# FD_Capacitance_Sensor_v09.net
KiCad netlist of a schematic drawn in EAGLE
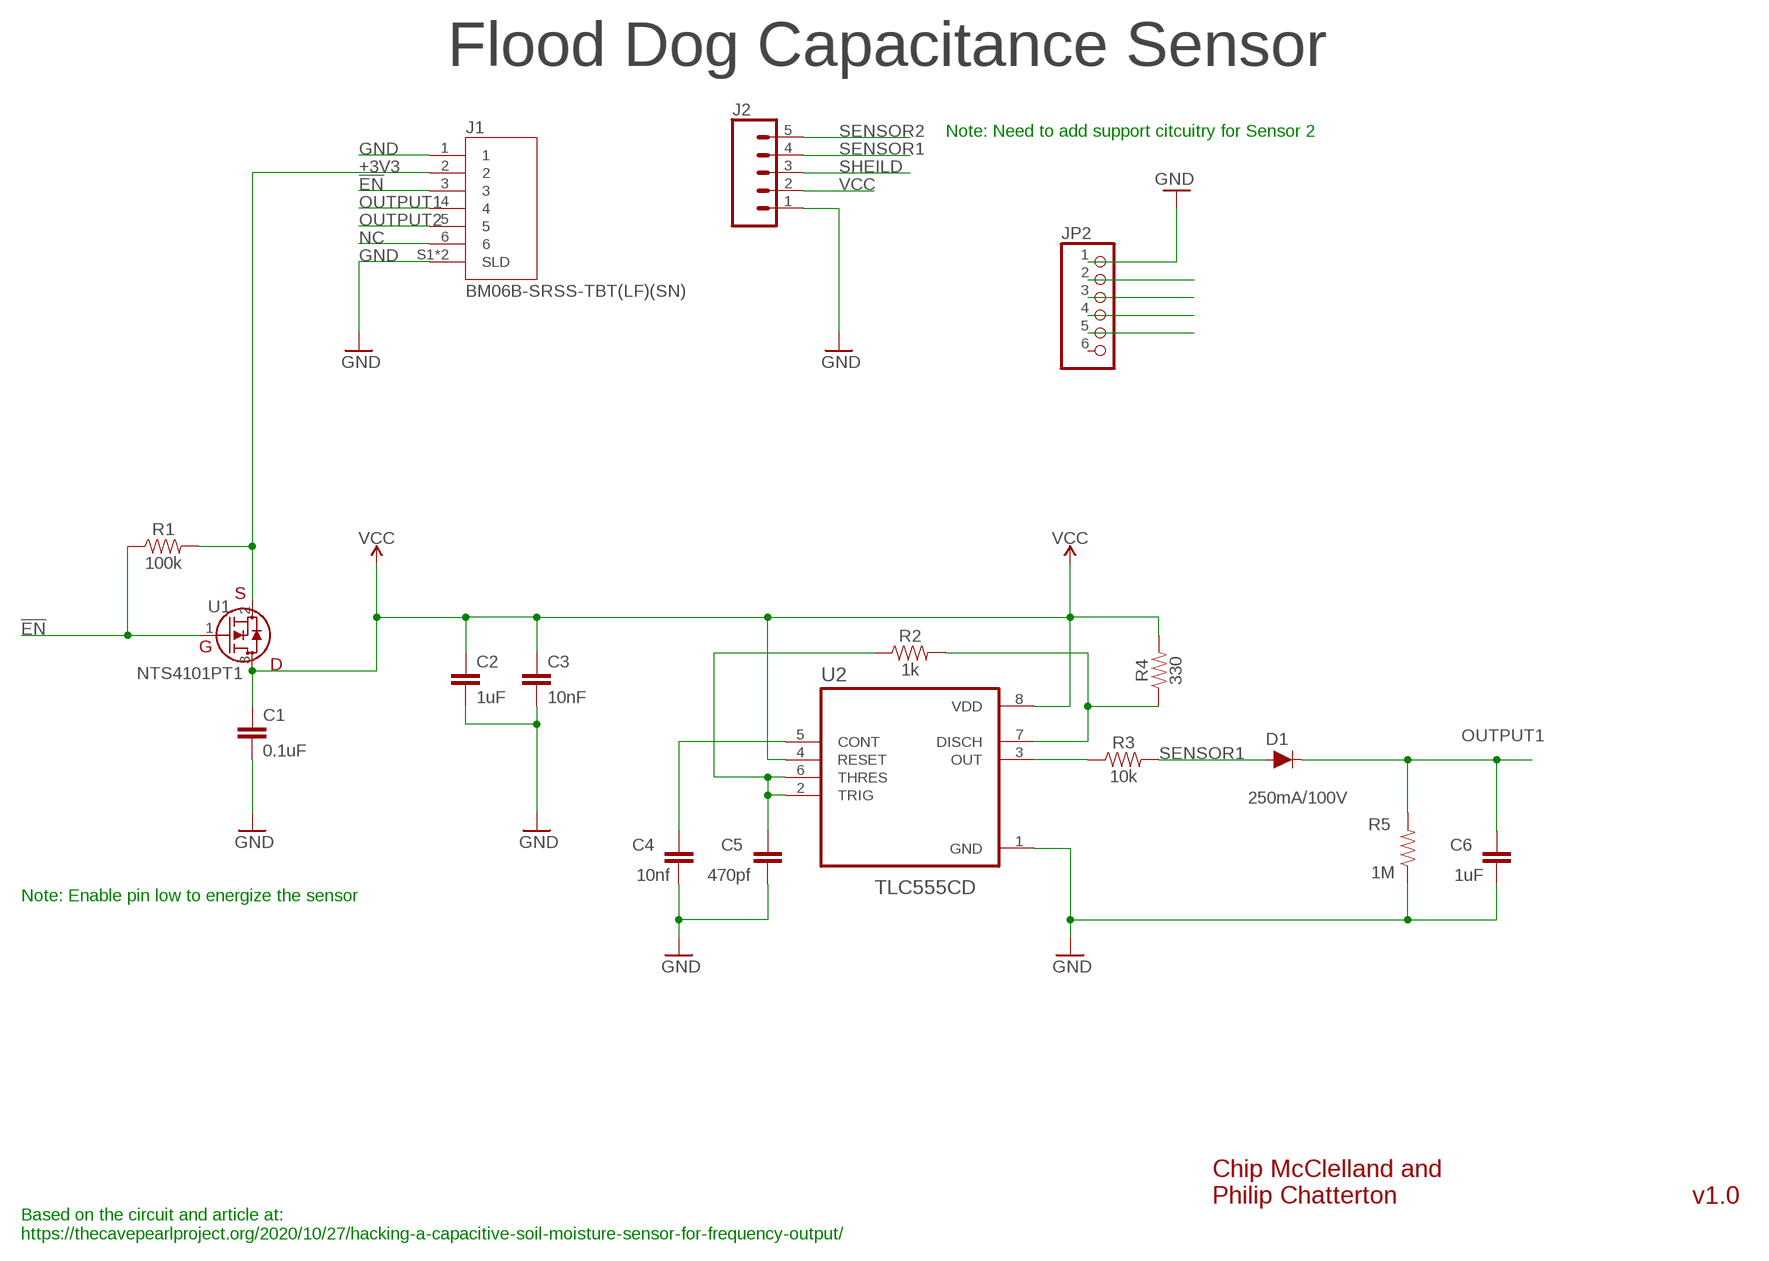
[diagram p0: schematic, sheet 1]

(export (version "E")
  (design (tool "Eeschema 10.0.6"))
  (components
    (comp (ref "C1")
      (value "0.1uF")
      (footprint "eagle-import:0805@1")
      (fields (field (name "HOUSEPART") "YES") (field (name "MPN") "MF-CAP-0805-0.1uF"))
      (libsource (lib "eagle-import") (part "CAP-MF-0.1UF-0805"))
    )
    (comp (ref "C2")
      (value "1uF")
      (footprint "eagle-import:0805@1")
      (fields (field (name "HOUSEPART") "yes") (field (name "MPN") "MF-CAP-0805-1uF"))
      (libsource (lib "eagle-import") (part "CAP-MF-1UF-0805"))
    )
    (comp (ref "C3")
      (value "10nF")
      (footprint "eagle-import:0805@1")
      (fields (field (name "HOUSEPART") "NO") (field (name "MPN") "C0805X103K1RAC3316"))
      (libsource (lib "eagle-import") (part "CAP-10NF-0805"))
    )
    (comp (ref "C4")
      (value "10nf")
      (footprint "eagle-import:C0805")
      (libsource (lib "eagle-import") (part "C-EUC0805"))
    )
    (comp (ref "C5")
      (value "470pf")
      (footprint "eagle-import:C0805")
      (libsource (lib "eagle-import") (part "C-EUC0805"))
    )
    (comp (ref "C6")
      (value "1uF")
      (footprint "eagle-import:C0805")
      (libsource (lib "eagle-import") (part "C-EUC0805"))
    )
    (comp (ref "D1")
      (value "250mA/100V")
      (footprint "eagle-import:SOD-323")
      (fields (field (name "MPN") "BAS16HT1G"))
      (libsource (lib "eagle-import") (part "DIODE-BAS16J"))
    )
    (comp (ref "J1")
      (value "BM06B-SRSS-TBT(LF)(SN)")
      (footprint "eagle-import:JST_BM06B-SRSS-TB(LF)(SN)")
      (libsource (lib "eagle-import") (part "BM06B-SRSS-TBT(LF)(SN)"))
    )
    (comp (ref "J2")
      (value "CONN_05SCREW")
      (footprint "eagle-import:SCREWTERMINAL-3.5MM-5")
      (libsource (lib "eagle-import") (part "CONN_05SCREW"))
    )
    (comp (ref "JP2")
      (value "PINHD-1X6B")
      (footprint "eagle-import:1X06-BIG")
      (libsource (lib "eagle-import") (part "PINHD-1X6B"))
    )
    (comp (ref "R1")
      (value "100k")
      (footprint "eagle-import:0805")
      (fields (field (name "MPN") "MF-RES-0805-100K") (field (name "MPN_1") "MF-RES-0805-100K"))
      (libsource (lib "eagle-import") (part "RESISTOR-MF-100K-0805"))
    )
    (comp (ref "R2")
      (value "1k")
      (footprint "eagle-import:0805")
      (fields (field (name "HOUSEPART") "YES") (field (name "MPN") "MF-RES-0805-1K"))
      (libsource (lib "eagle-import") (part "RESISTOR-MF-1K-0805"))
    )
    (comp (ref "R3")
      (value "10k")
      (footprint "eagle-import:0805")
      (fields (field (name "MPN") "MF-RES-0805-10K"))
      (libsource (lib "eagle-import") (part "RESISTOR-MF-10K-0805"))
    )
    (comp (ref "R4")
      (value "330")
      (footprint "eagle-import:0805")
      (fields (field (name "HOUSEPART") "YES") (field (name "MPN") "MF-RES-0805-330"))
      (libsource (lib "eagle-import") (part "RESISTOR-MF-330-0805"))
    )
    (comp (ref "R5")
      (value "1M")
      (footprint "eagle-import:0805")
      (fields (field (name "HOUSEPART") "YES") (field (name "MPN") "MF-RES-0805-1K"))
      (libsource (lib "eagle-import") (part "RESISTOR-MF-1K-0805"))
    )
    (comp (ref "U1")
      (value "NTS4101PT1")
      (footprint "eagle-import:SOT_101PT1_ONS")
      (libsource (lib "eagle-import") (part "NTS4101PT1"))
    )
    (comp (ref "U2")
      (value "TLC555CD")
      (footprint "eagle-import:SOIC127P599X175-8N")
      (fields (field (name "DIGI-KEY_PART_NUMBER") "296-52992-ND") (field (name "MF") "Texas Instruments"))
      (libsource (lib "eagle-import") (part "TLC555CD"))
    )
  )
  (nets
    (net (code "1") (name "/+3V3") (class "Default")
      (node (ref "J1") (pin "2") (pinfunction "2_2") (pintype "passive"))
      (node (ref "R1") (pin "2") (pinfunction "2_2") (pintype "passive"))
      (node (ref "U1") (pin "2") (pinfunction "S_2") (pintype "passive"))
    )
    (net (code "2") (name "/NC") (class "Default")
      (node (ref "J1") (pin "6") (pinfunction "6_6") (pintype "passive"))
    )
    (net (code "3") (name "/OUTPUT1") (class "Default")
      (node (ref "C6") (pin "2") (pinfunction "2_2") (pintype "passive"))
      (node (ref "D1") (pin "C") (pinfunction "C_C") (pintype "passive"))
      (node (ref "J1") (pin "4") (pinfunction "4_4") (pintype "passive"))
      (node (ref "R5") (pin "2") (pinfunction "2_2") (pintype "passive"))
    )
    (net (code "4") (name "/OUTPUT2") (class "Default")
      (node (ref "J1") (pin "5") (pinfunction "5_5") (pintype "passive"))
    )
    (net (code "5") (name "/SENSOR1") (class "Default")
      (node (ref "D1") (pin "A") (pinfunction "A_A") (pintype "passive"))
      (node (ref "J2") (pin "4") (pinfunction "4_4") (pintype "passive"))
      (node (ref "R3") (pin "2") (pinfunction "2_2") (pintype "passive"))
    )
    (net (code "6") (name "/SENSOR2") (class "Default")
      (node (ref "J2") (pin "5") (pinfunction "5_5") (pintype "passive"))
    )
    (net (code "7") (name "/SHEILD") (class "Default")
      (node (ref "J2") (pin "3") (pinfunction "3_3") (pintype "passive"))
    )
    (net (code "8") (name "/~{EN}") (class "Default")
      (node (ref "J1") (pin "3") (pinfunction "3_3") (pintype "passive"))
      (node (ref "R1") (pin "1") (pinfunction "1_1") (pintype "passive"))
      (node (ref "U1") (pin "1") (pinfunction "G_1") (pintype "passive"))
    )
    (net (code "9") (name "GND") (class "Default")
      (node (ref "C1") (pin "2") (pinfunction "2_2") (pintype "passive"))
      (node (ref "C2") (pin "2") (pinfunction "2_2") (pintype "passive"))
      (node (ref "C3") (pin "2") (pinfunction "2_2") (pintype "passive"))
      (node (ref "C4") (pin "1") (pinfunction "1_1") (pintype "passive"))
      (node (ref "C5") (pin "1") (pinfunction "1_1") (pintype "passive"))
      (node (ref "C6") (pin "1") (pinfunction "1_1") (pintype "passive"))
      (node (ref "J1") (pin "1") (pinfunction "1_1") (pintype "passive"))
      (node (ref "J1") (pin "S1") (pinfunction "SLD_S1") (pintype "passive"))
      (node (ref "J1") (pin "S2") (pinfunction "SLD_S2") (pintype "passive"))
      (node (ref "J2") (pin "1") (pinfunction "1_1") (pintype "passive"))
      (node (ref "JP2") (pin "1") (pinfunction "1_1") (pintype "passive"))
      (node (ref "R5") (pin "1") (pinfunction "1_1") (pintype "passive"))
      (node (ref "U2") (pin "1") (pinfunction "GND_1") (pintype "power_in"))
    )
    (net (code "10") (name "Net-(U2-CONT)") (class "Default")
      (node (ref "C4") (pin "2") (pinfunction "2_2") (pintype "passive"))
      (node (ref "U2") (pin "5") (pinfunction "CONT_5") (pintype "input"))
    )
    (net (code "11") (name "Net-(U2-DISCH)") (class "Default")
      (node (ref "R2") (pin "2") (pinfunction "2_2") (pintype "passive"))
      (node (ref "R4") (pin "1") (pinfunction "1_1") (pintype "passive"))
      (node (ref "U2") (pin "7") (pinfunction "DISCH_7") (pintype "output"))
    )
    (net (code "12") (name "Net-(U2-OUT)") (class "Default")
      (node (ref "R3") (pin "1") (pinfunction "1_1") (pintype "passive"))
      (node (ref "U2") (pin "3") (pinfunction "OUT_3") (pintype "output"))
    )
    (net (code "13") (name "Net-(U2-THRES)") (class "Default")
      (node (ref "C5") (pin "2") (pinfunction "2_2") (pintype "passive"))
      (node (ref "R2") (pin "1") (pinfunction "1_1") (pintype "passive"))
      (node (ref "U2") (pin "2") (pinfunction "TRIG_2") (pintype "input"))
      (node (ref "U2") (pin "6") (pinfunction "THRES_6") (pintype "input"))
    )
    (net (code "14") (name "VCC") (class "Default")
      (node (ref "C1") (pin "1") (pinfunction "1_1") (pintype "passive"))
      (node (ref "C2") (pin "1") (pinfunction "1_1") (pintype "passive"))
      (node (ref "C3") (pin "1") (pinfunction "1_1") (pintype "passive"))
      (node (ref "J2") (pin "2") (pinfunction "2_2") (pintype "passive"))
      (node (ref "R4") (pin "2") (pinfunction "2_2") (pintype "passive"))
      (node (ref "U1") (pin "3") (pinfunction "D_3") (pintype "passive"))
      (node (ref "U2") (pin "4") (pinfunction "RESET_4") (pintype "input"))
      (node (ref "U2") (pin "8") (pinfunction "VDD_8") (pintype "power_in"))
    )
    (net (code "15") (name "unconnected-(JP2-Pad2)") (class "Default")
      (node (ref "JP2") (pin "2") (pinfunction "2_2") (pintype "passive"))
    )
    (net (code "16") (name "unconnected-(JP2-Pad3)") (class "Default")
      (node (ref "JP2") (pin "3") (pinfunction "3_3") (pintype "passive"))
    )
    (net (code "17") (name "unconnected-(JP2-Pad4)") (class "Default")
      (node (ref "JP2") (pin "4") (pinfunction "4_4") (pintype "passive"))
    )
    (net (code "18") (name "unconnected-(JP2-Pad5)") (class "Default")
      (node (ref "JP2") (pin "5") (pinfunction "5_5") (pintype "passive"))
    )
    (net (code "19") (name "unconnected-(JP2-Pad6)") (class "Default")
      (node (ref "JP2") (pin "6") (pinfunction "6_6") (pintype "passive"))
    )
  )
)
